# MCU.net
KiCad netlist of a schematic drawn in Altium Designer
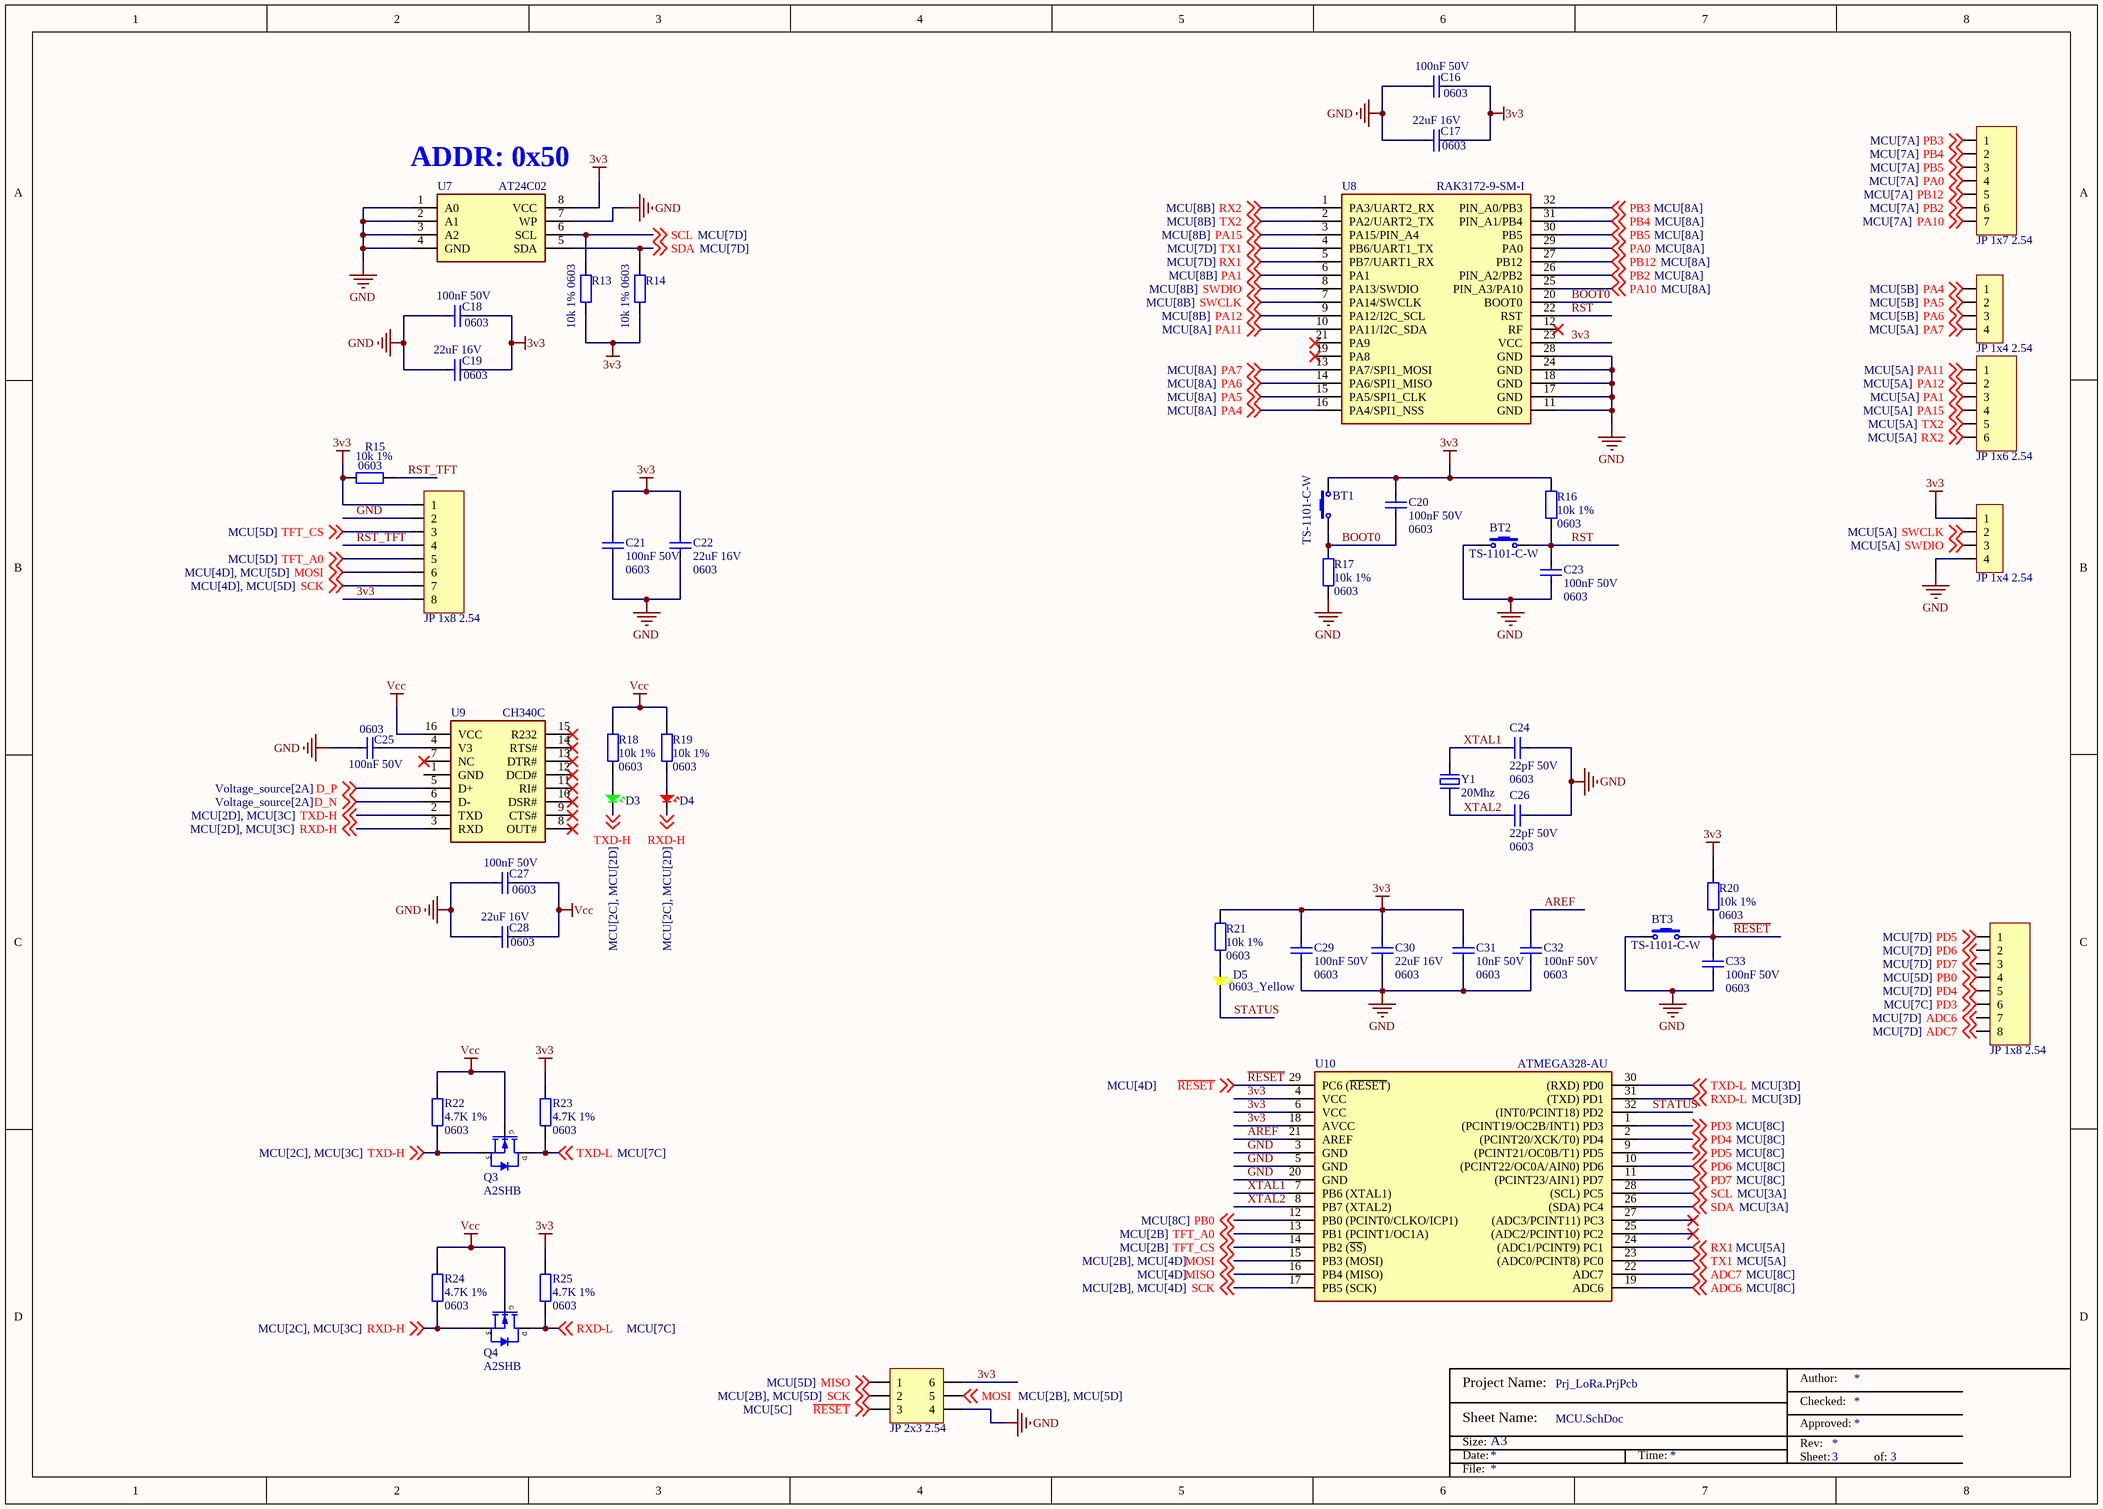
[diagram p0: MCU.SchDoc]

(export (version "E")
  (design (tool "Eeschema 10.0.6"))
  (components
    (comp (ref "BT1")
      (value "TS-1101-C-W")
      (footprint "button-2P-SMD-6x3x2.5")
      (fields (field (name "LCSC PART") "C318938") (field (name "MANUFACTURER") "XKB Connection"))
      (libsource (lib "binhbinh") (part "Button-2P"))
    )
    (comp (ref "BT2")
      (value "TS-1101-C-W")
      (footprint "button-2P-SMD-6x3x2.5")
      (fields (field (name "LCSC PART") "C318938") (field (name "MANUFACTURER") "XKB Connection"))
      (libsource (lib "binhbinh") (part "Button-2P"))
    )
    (comp (ref "BT3")
      (value "TS-1101-C-W")
      (footprint "button-2P-SMD-6x3x2.5")
      (fields (field (name "LCSC PART") "C318938") (field (name "MANUFACTURER") "XKB Connection"))
      (libsource (lib "binhbinh") (part "Button-2P"))
    )
    (comp (ref "C16")
      (value "100nF 50V")
      (footprint "C_0603")
      (description "50V 100nF X7R ±10% 0603 Multilayer Ceramic Capacitors MLCC - SMD/SMT ROHS")
      (fields
        (field (name "MANUFACTURER") "YAGEO")
        (field (name "MRF.PART") "CC0603KRX7R9BB104")
        (field (name "PACKAGE") "0603")
      )
      (libsource (lib "binhbinh") (part "C0603_MLCC_100nF_50V"))
    )
    (comp (ref "C17")
      (value "22uF 16V")
      (footprint "C_0603")
      (description "16V 22uF X5R ±20% 0603 Multilayer Ceramic Capacitors MLCC - SMD/SMT ROHS")
      (fields
        (field (name "MANUFACTURER") "Samsung Electro-Mechanics")
        (field (name "MRF.PART") "CL10A226MO7JZNC")
        (field (name "PACKAGE") "0603")
      )
      (libsource (lib "binhbinh") (part "C0603_MLCC_22uF_16V"))
    )
    (comp (ref "C18")
      (value "100nF 50V")
      (footprint "C_0603")
      (description "50V 100nF X7R ±10% 0603 Multilayer Ceramic Capacitors MLCC - SMD/SMT ROHS")
      (fields
        (field (name "MANUFACTURER") "YAGEO")
        (field (name "MRF.PART") "CC0603KRX7R9BB104")
        (field (name "PACKAGE") "0603")
      )
      (libsource (lib "binhbinh") (part "C0603_MLCC_100nF_50V"))
    )
    (comp (ref "C19")
      (value "22uF 16V")
      (footprint "C_0603")
      (description "16V 22uF X5R ±20% 0603 Multilayer Ceramic Capacitors MLCC - SMD/SMT ROHS")
      (fields
        (field (name "MANUFACTURER") "Samsung Electro-Mechanics")
        (field (name "MRF.PART") "CL10A226MO7JZNC")
        (field (name "PACKAGE") "0603")
      )
      (libsource (lib "binhbinh") (part "C0603_MLCC_22uF_16V"))
    )
    (comp (ref "C20")
      (value "100nF 50V")
      (footprint "C_0603")
      (description "50V 100nF X7R ±10% 0603 Multilayer Ceramic Capacitors MLCC - SMD/SMT ROHS")
      (fields
        (field (name "MANUFACTURER") "YAGEO")
        (field (name "MRF.PART") "CC0603KRX7R9BB104")
        (field (name "PACKAGE") "0603")
      )
      (libsource (lib "binhbinh") (part "C0603_MLCC_100nF_50V"))
    )
    (comp (ref "C21")
      (value "100nF 50V")
      (footprint "C_0603")
      (description "50V 100nF X7R ±10% 0603 Multilayer Ceramic Capacitors MLCC - SMD/SMT ROHS")
      (fields
        (field (name "MANUFACTURER") "YAGEO")
        (field (name "MRF.PART") "CC0603KRX7R9BB104")
        (field (name "PACKAGE") "0603")
      )
      (libsource (lib "binhbinh") (part "C0603_MLCC_100nF_50V"))
    )
    (comp (ref "C22")
      (value "22uF 16V")
      (footprint "C_0603")
      (description "16V 22uF X5R ±20% 0603 Multilayer Ceramic Capacitors MLCC - SMD/SMT ROHS")
      (fields
        (field (name "MANUFACTURER") "Samsung Electro-Mechanics")
        (field (name "MRF.PART") "CL10A226MO7JZNC")
        (field (name "PACKAGE") "0603")
      )
      (libsource (lib "binhbinh") (part "C0603_MLCC_22uF_16V"))
    )
    (comp (ref "C23")
      (value "100nF 50V")
      (footprint "C_0603")
      (description "50V 100nF X7R ±10% 0603 Multilayer Ceramic Capacitors MLCC - SMD/SMT ROHS")
      (fields
        (field (name "MANUFACTURER") "YAGEO")
        (field (name "MRF.PART") "CC0603KRX7R9BB104")
        (field (name "PACKAGE") "0603")
      )
      (libsource (lib "binhbinh") (part "C0603_MLCC_100nF_50V"))
    )
    (comp (ref "C24")
      (value "22pF 50V")
      (footprint "C_0603")
      (description "50V 22pF NP0 ±5% 0603 Multilayer Ceramic Capacitors MLCC - SMD/SMT ROHS")
      (fields
        (field (name "MANUFACTURER") "YAGEO")
        (field (name "MRF.PART") "CC0603JRNPO9BN220")
        (field (name "PACKAGE") "0603")
      )
      (libsource (lib "binhbinh") (part "C0603_MLCC_22pF_50V"))
    )
    (comp (ref "C25")
      (value "100nF 50V")
      (footprint "C_0603")
      (description "50V 100nF X7R ±10% 0603 Multilayer Ceramic Capacitors MLCC - SMD/SMT ROHS")
      (fields
        (field (name "MANUFACTURER") "YAGEO")
        (field (name "MRF.PART") "CC0603KRX7R9BB104")
        (field (name "PACKAGE") "0603")
      )
      (libsource (lib "binhbinh") (part "C0603_MLCC_100nF_50V"))
    )
    (comp (ref "C26")
      (value "22pF 50V")
      (footprint "C_0603")
      (description "50V 22pF NP0 ±5% 0603 Multilayer Ceramic Capacitors MLCC - SMD/SMT ROHS")
      (fields
        (field (name "MANUFACTURER") "YAGEO")
        (field (name "MRF.PART") "CC0603JRNPO9BN220")
        (field (name "PACKAGE") "0603")
      )
      (libsource (lib "binhbinh") (part "C0603_MLCC_22pF_50V"))
    )
    (comp (ref "C27")
      (value "100nF 50V")
      (footprint "C_0603")
      (description "50V 100nF X7R ±10% 0603 Multilayer Ceramic Capacitors MLCC - SMD/SMT ROHS")
      (fields
        (field (name "MANUFACTURER") "YAGEO")
        (field (name "MRF.PART") "CC0603KRX7R9BB104")
        (field (name "PACKAGE") "0603")
      )
      (libsource (lib "binhbinh") (part "C0603_MLCC_100nF_50V"))
    )
    (comp (ref "C28")
      (value "22uF 16V")
      (footprint "C_0603")
      (description "16V 22uF X5R ±20% 0603 Multilayer Ceramic Capacitors MLCC - SMD/SMT ROHS")
      (fields
        (field (name "MANUFACTURER") "Samsung Electro-Mechanics")
        (field (name "MRF.PART") "CL10A226MO7JZNC")
        (field (name "PACKAGE") "0603")
      )
      (libsource (lib "binhbinh") (part "C0603_MLCC_22uF_16V"))
    )
    (comp (ref "C29")
      (value "100nF 50V")
      (footprint "C_0603")
      (description "50V 100nF X7R ±10% 0603 Multilayer Ceramic Capacitors MLCC - SMD/SMT ROHS")
      (fields
        (field (name "MANUFACTURER") "YAGEO")
        (field (name "MRF.PART") "CC0603KRX7R9BB104")
        (field (name "PACKAGE") "0603")
      )
      (libsource (lib "binhbinh") (part "C0603_MLCC_100nF_50V"))
    )
    (comp (ref "C30")
      (value "22uF 16V")
      (footprint "C_0603")
      (description "16V 22uF X5R ±20% 0603 Multilayer Ceramic Capacitors MLCC - SMD/SMT ROHS")
      (fields
        (field (name "MANUFACTURER") "Samsung Electro-Mechanics")
        (field (name "MRF.PART") "CL10A226MO7JZNC")
        (field (name "PACKAGE") "0603")
      )
      (libsource (lib "binhbinh") (part "C0603_MLCC_22uF_16V"))
    )
    (comp (ref "C31")
      (value "10nF 50V")
      (footprint "C_0603")
      (description "50V 10nF X7R ±10% 0603 Multilayer Ceramic Capacitors MLCC - SMD/SMT ROHS")
      (fields
        (field (name "MANUFACTURER") "YAGEO")
        (field (name "MRF.PART") "CC0603KRX7R9BB103")
        (field (name "PACKAGE") "0603")
      )
      (libsource (lib "binhbinh") (part "C0603_MLCC_10nF_50V"))
    )
    (comp (ref "C32")
      (value "100nF 50V")
      (footprint "C_0603")
      (description "50V 100nF X7R ±10% 0603 Multilayer Ceramic Capacitors MLCC - SMD/SMT ROHS")
      (fields
        (field (name "MANUFACTURER") "YAGEO")
        (field (name "MRF.PART") "CC0603KRX7R9BB104")
        (field (name "PACKAGE") "0603")
      )
      (libsource (lib "binhbinh") (part "C0603_MLCC_100nF_50V"))
    )
    (comp (ref "C33")
      (value "100nF 50V")
      (footprint "C_0603")
      (description "50V 100nF X7R ±10% 0603 Multilayer Ceramic Capacitors MLCC - SMD/SMT ROHS")
      (fields
        (field (name "MANUFACTURER") "YAGEO")
        (field (name "MRF.PART") "CC0603KRX7R9BB104")
        (field (name "PACKAGE") "0603")
      )
      (libsource (lib "binhbinh") (part "C0603_MLCC_100nF_50V"))
    )
    (comp (ref "D3")
      (value "0603 GREEN")
      (footprint "LED0603_GREEN")
      (fields (field (name "MANUFACTURER") "Amicc") (field (name "MRF.PART") "A-SP192DGHC-C01-4T"))
      (libsource (lib "binhbinh") (part "L0603_GREEN"))
    )
    (comp (ref "D4")
      (value "0603 RED")
      (footprint "LED0603_RED")
      (fields (field (name "MANUFACTURER") "XINGLIGHT") (field (name "MRF.PART") "XL-1608SURC-06"))
      (libsource (lib "binhbinh") (part "L0603_RED"))
    )
    (comp (ref "D5")
      (value "0603_Yellow")
      (footprint "LED0603_YELLOW")
      (fields
        (field (name "LCSC PART") "C965802")
        (field (name "MRF.PART") "XL-1608UYC-06")
        (field (name "MANUFACTURER") "XINGLIGHT")
      )
      (libsource (lib "binhbinh") (part "L0603_Yellow"))
    )
    (comp (ref "JP2")
      (value "JP 1x7 2.54")
      (footprint "JP 1x7 CT")
      (description "Cắm")
      (libsource (lib "Altium_Lib_by_KhueNguyenCreator") (part "JP 1x7 2.54 Cai Thang"))
    )
    (comp (ref "JP3")
      (value "JP 1x4 2.54")
      (footprint "JP 1x4 CT")
      (description "Cắm")
      (libsource (lib "Altium_Lib_by_KhueNguyenCreator") (part "JP 1x4 2.54 Cai Thang"))
    )
    (comp (ref "JP4")
      (value "JP 1x6 2.54")
      (footprint "JP 1x6 CT")
      (description "Cắm")
      (libsource (lib "Altium_Lib_by_KhueNguyenCreator") (part "JP 1x6 2.54 Cai Thang"))
    )
    (comp (ref "JP5")
      (value "JP 1x8 2.54")
      (footprint "JP 1x8 CT")
      (description "Cắm")
      (libsource (lib "Altium_Lib_by_KhueNguyenCreator") (part "JP 1x8 2.54 Cai Thang"))
    )
    (comp (ref "JP6")
      (value "JP 1x4 2.54")
      (footprint "JP 1x4 CT")
      (description "Cắm")
      (libsource (lib "Altium_Lib_by_KhueNguyenCreator") (part "JP 1x4 2.54 Cai Thang"))
    )
    (comp (ref "JP7")
      (value "JP 1x8 2.54")
      (footprint "JP 1x8 CT")
      (description "Cắm")
      (libsource (lib "Altium_Lib_by_KhueNguyenCreator") (part "JP 1x8 2.54 Cai Thang"))
    )
    (comp (ref "JP8")
      (value "JP 2x3 2.54")
      (footprint "JP 2x3 DT")
      (description "Cắm")
      (libsource (lib "Altium_Lib_by_KhueNguyenCreator") (part "JP 2x3 2.54 Duc Thang"))
    )
    (comp (ref "Q3")
      (value "A2SHB")
      (footprint "SOT23-3")
      (description "20V 3A 900mW 60mΩ@4.5V 1V@50uA 1 N-Channel SOT-23 MOSFETs ROHS")
      (fields (field (name "LCSC PART") "C2905536") (field (name "MRF.PART") "JSM2302A-A2SHB"))
      (libsource (lib "binhbinh") (part "A2SHB"))
    )
    (comp (ref "Q4")
      (value "A2SHB")
      (footprint "SOT23-3")
      (description "20V 3A 900mW 60mΩ@4.5V 1V@50uA 1 N-Channel SOT-23 MOSFETs ROHS")
      (fields (field (name "LCSC PART") "C2905536") (field (name "MRF.PART") "JSM2302A-A2SHB"))
      (libsource (lib "binhbinh") (part "A2SHB"))
    )
    (comp (ref "R13")
      (value "10k 1%")
      (footprint "R_0603")
      (description "100mW Thick Film Resistor 75V ±100ppm/℃ ±1% 10kΩ 0603 Chip Resistor - Surface Mount ROHS")
      (fields
        (field (name "LCSC PART") "C98220")
        (field (name "MRF.PART") "RC0603FR-0710KL")
        (field (name "PACKAGE") "0603")
      )
      (libsource (lib "binhbinh") (part "R0603_10k"))
    )
    (comp (ref "R14")
      (value "10k 1%")
      (footprint "R_0603")
      (description "100mW Thick Film Resistor 75V ±100ppm/℃ ±1% 10kΩ 0603 Chip Resistor - Surface Mount ROHS")
      (fields
        (field (name "LCSC PART") "C98220")
        (field (name "MRF.PART") "RC0603FR-0710KL")
        (field (name "PACKAGE") "0603")
      )
      (libsource (lib "binhbinh") (part "R0603_10k"))
    )
    (comp (ref "R15")
      (value "10k 1%")
      (footprint "R_0603")
      (description "100mW Thick Film Resistor 75V ±100ppm/℃ ±1% 10kΩ 0603 Chip Resistor - Surface Mount ROHS")
      (fields
        (field (name "LCSC PART") "C98220")
        (field (name "MRF.PART") "RC0603FR-0710KL")
        (field (name "PACKAGE") "0603")
      )
      (libsource (lib "") (part "R0603_10k_1"))
    )
    (comp (ref "R16")
      (value "10k 1%")
      (footprint "R_0603")
      (description "100mW Thick Film Resistor 75V ±100ppm/℃ ±1% 10kΩ 0603 Chip Resistor - Surface Mount ROHS")
      (fields
        (field (name "LCSC PART") "C98220")
        (field (name "MRF.PART") "RC0603FR-0710KL")
        (field (name "PACKAGE") "0603")
      )
      (libsource (lib "binhbinh") (part "R0603_10k"))
    )
    (comp (ref "R17")
      (value "10k 1%")
      (footprint "R_0603")
      (description "100mW Thick Film Resistor 75V ±100ppm/℃ ±1% 10kΩ 0603 Chip Resistor - Surface Mount ROHS")
      (fields
        (field (name "LCSC PART") "C98220")
        (field (name "MRF.PART") "RC0603FR-0710KL")
        (field (name "PACKAGE") "0603")
      )
      (libsource (lib "binhbinh") (part "R0603_10k"))
    )
    (comp (ref "R18")
      (value "10k 1%")
      (footprint "R_0603")
      (description "100mW Thick Film Resistor 75V ±100ppm/℃ ±1% 10kΩ 0603 Chip Resistor - Surface Mount ROHS")
      (fields
        (field (name "LCSC PART") "C98220")
        (field (name "MRF.PART") "RC0603FR-0710KL")
        (field (name "PACKAGE") "0603")
      )
      (libsource (lib "binhbinh") (part "R0603_10k"))
    )
    (comp (ref "R19")
      (value "10k 1%")
      (footprint "R_0603")
      (description "100mW Thick Film Resistor 75V ±100ppm/℃ ±1% 10kΩ 0603 Chip Resistor - Surface Mount ROHS")
      (fields
        (field (name "LCSC PART") "C98220")
        (field (name "MRF.PART") "RC0603FR-0710KL")
        (field (name "PACKAGE") "0603")
      )
      (libsource (lib "binhbinh") (part "R0603_10k"))
    )
    (comp (ref "R20")
      (value "10k 1%")
      (footprint "R_0603")
      (description "100mW Thick Film Resistor 75V ±100ppm/℃ ±1% 10kΩ 0603 Chip Resistor - Surface Mount ROHS")
      (fields
        (field (name "LCSC PART") "C98220")
        (field (name "MRF.PART") "RC0603FR-0710KL")
        (field (name "PACKAGE") "0603")
      )
      (libsource (lib "binhbinh") (part "R0603_10k"))
    )
    (comp (ref "R21")
      (value "10k 1%")
      (footprint "R_0603")
      (description "100mW Thick Film Resistor 75V ±100ppm/℃ ±1% 10kΩ 0603 Chip Resistor - Surface Mount ROHS")
      (fields
        (field (name "LCSC PART") "C98220")
        (field (name "MRF.PART") "RC0603FR-0710KL")
        (field (name "PACKAGE") "0603")
      )
      (libsource (lib "binhbinh") (part "R0603_10k"))
    )
    (comp (ref "R22")
      (value "4.7K 1%")
      (footprint "R_0603")
      (description "4.7 kOhms ±1% 0.1W, 1/10W Chip Resistor 0603 (1608 Metric) Moisture Resistant Thick Film")
      (fields
        (field (name "MANUFACTURER") "YAGEO")
        (field (name "MRF.PART") "RC0603FR-074K7L")
        (field (name "PACKAGE") "0603")
      )
      (libsource (lib "binhbinh") (part "R0603_4.7K"))
    )
    (comp (ref "R23")
      (value "4.7K 1%")
      (footprint "R_0603")
      (description "4.7 kOhms ±1% 0.1W, 1/10W Chip Resistor 0603 (1608 Metric) Moisture Resistant Thick Film")
      (fields
        (field (name "MANUFACTURER") "YAGEO")
        (field (name "MRF.PART") "RC0603FR-074K7L")
        (field (name "PACKAGE") "0603")
      )
      (libsource (lib "binhbinh") (part "R0603_4.7K"))
    )
    (comp (ref "R24")
      (value "4.7K 1%")
      (footprint "R_0603")
      (description "4.7 kOhms ±1% 0.1W, 1/10W Chip Resistor 0603 (1608 Metric) Moisture Resistant Thick Film")
      (fields
        (field (name "MANUFACTURER") "YAGEO")
        (field (name "MRF.PART") "RC0603FR-074K7L")
        (field (name "PACKAGE") "0603")
      )
      (libsource (lib "binhbinh") (part "R0603_4.7K"))
    )
    (comp (ref "R25")
      (value "4.7K 1%")
      (footprint "R_0603")
      (description "4.7 kOhms ±1% 0.1W, 1/10W Chip Resistor 0603 (1608 Metric) Moisture Resistant Thick Film")
      (fields
        (field (name "MANUFACTURER") "YAGEO")
        (field (name "MRF.PART") "RC0603FR-074K7L")
        (field (name "PACKAGE") "0603")
      )
      (libsource (lib "binhbinh") (part "R0603_4.7K"))
    )
    (comp (ref "U7")
      (value "AT24C02")
      (footprint "SOP-8")
      (description "2Kbit 1MHz I2C SOP-8 EEPROM ROHS")
      (fields (field (name "LCSC PART") "C7470930") (field (name "MANUFACTURER") "HXY MOSFET"))
      (libsource (lib "binhbinh") (part "AT24C02"))
    )
    (comp (ref "U8")
      (value "RAK3172-9-SM-I")
      (footprint "RAK3172")
      (description "15km SMD,15.5x15mm LoRa Modules ROHS, with IPEX")
      (fields (field (name "LCSC PART") "C19723905") (field (name "MANUFACTURER") "RAKwireless"))
      (libsource (lib "binhbinh") (part "RAK3172-9-SM-I"))
    )
    (comp (ref "U9")
      (value "CH340C")
      (footprint "CH340C")
      (description "2Mbps Transceiver USB 2.0 SOP-16 USB Converters ROHS")
      (fields (field (name "LCSC PART") "C84681") (field (name "MANUFACTURER") "WCH"))
      (libsource (lib "binhbinh") (part "CH340C"))
    )
    (comp (ref "U10")
      (value "ATMEGA328-AU")
      (footprint "TQFP-32(7x7)")
      (description "AVR 20MHz TQFP-32(7x7) Microcontrollers (MCU/MPU/SOC) ROHS")
      (fields (field (name "LCSC PART") "C618731") (field (name "MANUFACTURER") "MICROCHIP"))
      (libsource (lib "binhbinh") (part "ATMEGA328-AU"))
    )
    (comp (ref "Y1")
      (value "20Mhz")
      (footprint "HC-49S-SMD")
      (description "20MHz Crystal Oscillator 20pF ±20ppm ±30ppm HC-49S-SMD Crystals ROHS")
      (fields (field (name "LCSC PART") "C18213020") (field (name "MRF.PART") "H6OEL89CSC-SUGYLC-20M"))
      (libsource (lib "binhbinh") (part "20Mhz-2P"))
    )
  )
  (nets
    (net (code "1") (name "/AREF") (class "Default")
      (node (ref "C32") (pin "2") (pinfunction "2_2") (pintype "passive"))
      (node (ref "U10") (pin "21") (pinfunction "AREF_21") (pintype "passive"))
    )
    (net (code "2") (name "/BOOT0") (class "Default")
      (node (ref "BT1") (pin "1") (pinfunction "1_1") (pintype "passive"))
      (node (ref "C20") (pin "2") (pinfunction "2_2") (pintype "passive"))
      (node (ref "R17") (pin "2") (pinfunction "2_2") (pintype "passive"))
      (node (ref "U8") (pin "20") (pinfunction "BOOT0_20") (pintype "passive"))
    )
    (net (code "3") (name "/RST") (class "Default")
      (node (ref "BT2") (pin "2") (pinfunction "2_2") (pintype "passive"))
      (node (ref "C23") (pin "2") (pinfunction "2_2") (pintype "passive"))
      (node (ref "R16") (pin "1") (pinfunction "1_1") (pintype "passive"))
      (node (ref "U8") (pin "22") (pinfunction "RST_22") (pintype "passive"))
    )
    (net (code "4") (name "/RST_TFT") (class "Default")
      (node (ref "JP5") (pin "4") (pinfunction "4_4") (pintype "passive"))
      (node (ref "R15") (pin "2") (pinfunction "2_2") (pintype "passive"))
    )
    (net (code "5") (name "/STATUS") (class "Default")
      (node (ref "D5") (pin "2") (pinfunction "2_2") (pintype "passive"))
      (node (ref "U10") (pin "32") (pinfunction "(INT0/PCINT18)_PD2_32") (pintype "passive"))
    )
    (net (code "6") (name "/XTAL1") (class "Default")
      (node (ref "C24") (pin "2") (pinfunction "2_2") (pintype "passive"))
      (node (ref "U10") (pin "7") (pinfunction "PB6_(XTAL1)_7") (pintype "passive"))
      (node (ref "Y1") (pin "2") (pinfunction "2_2") (pintype "passive"))
    )
    (net (code "7") (name "/XTAL2") (class "Default")
      (node (ref "C26") (pin "2") (pinfunction "2_2") (pintype "passive"))
      (node (ref "U10") (pin "8") (pinfunction "PB7_(XTAL2)_8") (pintype "passive"))
      (node (ref "Y1") (pin "1") (pinfunction "1_1") (pintype "passive"))
    )
    (net (code "8") (name "3v3") (class "Default")
      (node (ref "BT1") (pin "2") (pinfunction "2_2") (pintype "passive"))
      (node (ref "C16") (pin "2") (pinfunction "2_2") (pintype "passive"))
      (node (ref "C17") (pin "1") (pinfunction "1_1") (pintype "passive"))
      (node (ref "C18") (pin "2") (pinfunction "2_2") (pintype "passive"))
      (node (ref "C19") (pin "1") (pinfunction "1_1") (pintype "passive"))
      (node (ref "C20") (pin "1") (pinfunction "1_1") (pintype "passive"))
      (node (ref "C21") (pin "2") (pinfunction "2_2") (pintype "passive"))
      (node (ref "C22") (pin "1") (pinfunction "1_1") (pintype "passive"))
      (node (ref "C29") (pin "2") (pinfunction "2_2") (pintype "passive"))
      (node (ref "C30") (pin "1") (pinfunction "1_1") (pintype "passive"))
      (node (ref "C31") (pin "2") (pinfunction "2_2") (pintype "passive"))
      (node (ref "JP5") (pin "1") (pinfunction "1_1") (pintype "passive"))
      (node (ref "JP5") (pin "8") (pinfunction "8_8") (pintype "passive"))
      (node (ref "JP6") (pin "1") (pinfunction "1_1") (pintype "passive"))
      (node (ref "JP8") (pin "6") (pinfunction "6_6") (pintype "passive"))
      (node (ref "R13") (pin "1") (pinfunction "1_1") (pintype "passive"))
      (node (ref "R14") (pin "1") (pinfunction "1_1") (pintype "passive"))
      (node (ref "R15") (pin "1") (pinfunction "1_1") (pintype "passive"))
      (node (ref "R16") (pin "2") (pinfunction "2_2") (pintype "passive"))
      (node (ref "R20") (pin "2") (pinfunction "2_2") (pintype "passive"))
      (node (ref "R21") (pin "2") (pinfunction "2_2") (pintype "passive"))
      (node (ref "R23") (pin "2") (pinfunction "2_2") (pintype "passive"))
      (node (ref "R25") (pin "2") (pinfunction "2_2") (pintype "passive"))
      (node (ref "U10") (pin "18") (pinfunction "AVCC_18") (pintype "passive"))
      (node (ref "U10") (pin "4") (pinfunction "VCC_4") (pintype "passive"))
      (node (ref "U10") (pin "6") (pinfunction "VCC_6") (pintype "passive"))
      (node (ref "U7") (pin "8") (pinfunction "VCC_8") (pintype "passive"))
      (node (ref "U8") (pin "23") (pinfunction "VCC_23") (pintype "passive"))
    )
    (net (code "9") (name "ADC6") (class "Default")
      (node (ref "JP7") (pin "7") (pinfunction "7_7") (pintype "passive"))
      (node (ref "U10") (pin "19") (pinfunction "ADC6_19") (pintype "passive"))
    )
    (net (code "10") (name "ADC7") (class "Default")
      (node (ref "JP7") (pin "8") (pinfunction "8_8") (pintype "passive"))
      (node (ref "U10") (pin "22") (pinfunction "ADC7_22") (pintype "passive"))
    )
    (net (code "11") (name "D_N") (class "Default")
      (node (ref "U9") (pin "6") (pinfunction "D-_6") (pintype "passive"))
    )
    (net (code "12") (name "D_P") (class "Default")
      (node (ref "U9") (pin "5") (pinfunction "D+_5") (pintype "passive"))
    )
    (net (code "13") (name "GND") (class "Default")
      (node (ref "BT2") (pin "1") (pinfunction "1_1") (pintype "passive"))
      (node (ref "BT3") (pin "1") (pinfunction "1_1") (pintype "passive"))
      (node (ref "C16") (pin "1") (pinfunction "1_1") (pintype "passive"))
      (node (ref "C17") (pin "2") (pinfunction "2_2") (pintype "passive"))
      (node (ref "C18") (pin "1") (pinfunction "1_1") (pintype "passive"))
      (node (ref "C19") (pin "2") (pinfunction "2_2") (pintype "passive"))
      (node (ref "C21") (pin "1") (pinfunction "1_1") (pintype "passive"))
      (node (ref "C22") (pin "2") (pinfunction "2_2") (pintype "passive"))
      (node (ref "C23") (pin "1") (pinfunction "1_1") (pintype "passive"))
      (node (ref "C24") (pin "1") (pinfunction "1_1") (pintype "passive"))
      (node (ref "C25") (pin "2") (pinfunction "2_2") (pintype "passive"))
      (node (ref "C26") (pin "1") (pinfunction "1_1") (pintype "passive"))
      (node (ref "C27") (pin "1") (pinfunction "1_1") (pintype "passive"))
      (node (ref "C28") (pin "2") (pinfunction "2_2") (pintype "passive"))
      (node (ref "C29") (pin "1") (pinfunction "1_1") (pintype "passive"))
      (node (ref "C30") (pin "2") (pinfunction "2_2") (pintype "passive"))
      (node (ref "C31") (pin "1") (pinfunction "1_1") (pintype "passive"))
      (node (ref "C32") (pin "1") (pinfunction "1_1") (pintype "passive"))
      (node (ref "C33") (pin "1") (pinfunction "1_1") (pintype "passive"))
      (node (ref "JP5") (pin "2") (pinfunction "2_2") (pintype "passive"))
      (node (ref "JP6") (pin "4") (pinfunction "4_4") (pintype "passive"))
      (node (ref "JP8") (pin "4") (pinfunction "4_4") (pintype "passive"))
      (node (ref "R17") (pin "1") (pinfunction "1_1") (pintype "passive"))
      (node (ref "U10") (pin "20") (pinfunction "GND_20") (pintype "passive"))
      (node (ref "U10") (pin "3") (pinfunction "GND_3") (pintype "passive"))
      (node (ref "U10") (pin "5") (pinfunction "GND_5") (pintype "passive"))
      (node (ref "U7") (pin "1") (pinfunction "A0_1") (pintype "passive"))
      (node (ref "U7") (pin "2") (pinfunction "A1_2") (pintype "passive"))
      (node (ref "U7") (pin "3") (pinfunction "A2_3") (pintype "passive"))
      (node (ref "U7") (pin "4") (pinfunction "GND_4") (pintype "passive"))
      (node (ref "U7") (pin "7") (pinfunction "WP_7") (pintype "passive"))
      (node (ref "U8") (pin "11") (pinfunction "GND_11") (pintype "passive"))
      (node (ref "U8") (pin "17") (pinfunction "GND_17") (pintype "passive"))
      (node (ref "U8") (pin "18") (pinfunction "GND_18") (pintype "passive"))
      (node (ref "U8") (pin "24") (pinfunction "GND_24") (pintype "passive"))
      (node (ref "U8") (pin "28") (pinfunction "GND_28") (pintype "passive"))
    )
    (net (code "14") (name "MISO") (class "Default")
      (node (ref "JP8") (pin "1") (pinfunction "1_1") (pintype "passive"))
      (node (ref "U10") (pin "16") (pinfunction "PB4_(MISO)_16") (pintype "passive"))
    )
    (net (code "15") (name "MOSI") (class "Default")
      (node (ref "JP5") (pin "6") (pinfunction "6_6") (pintype "passive"))
      (node (ref "JP8") (pin "5") (pinfunction "5_5") (pintype "passive"))
      (node (ref "U10") (pin "15") (pinfunction "PB3_(MOSI)_15") (pintype "passive"))
    )
    (net (code "16") (name "Net-(D3-Pad1)") (class "Default")
      (node (ref "D3") (pin "1") (pinfunction "1_1") (pintype "passive"))
      (node (ref "R18") (pin "1") (pinfunction "1_1") (pintype "passive"))
    )
    (net (code "17") (name "Net-(D4-Pad1)") (class "Default")
      (node (ref "D4") (pin "1") (pinfunction "1_1") (pintype "passive"))
      (node (ref "R19") (pin "1") (pinfunction "1_1") (pintype "passive"))
    )
    (net (code "18") (name "Net-(D5-Pad1)") (class "Default")
      (node (ref "D5") (pin "1") (pinfunction "1_1") (pintype "passive"))
      (node (ref "R21") (pin "1") (pinfunction "1_1") (pintype "passive"))
    )
    (net (code "19") (name "Net-(U9-V3)") (class "Default")
      (node (ref "C25") (pin "1") (pinfunction "1_1") (pintype "passive"))
      (node (ref "U9") (pin "4") (pinfunction "V3_4") (pintype "passive"))
    )
    (net (code "20") (name "PA0") (class "Default")
      (node (ref "JP2") (pin "4") (pinfunction "4_4") (pintype "passive"))
      (node (ref "U8") (pin "29") (pinfunction "PA0_29") (pintype "passive"))
    )
    (net (code "21") (name "PA1") (class "Default")
      (node (ref "JP4") (pin "3") (pinfunction "3_3") (pintype "passive"))
      (node (ref "U8") (pin "6") (pinfunction "PA1_6") (pintype "passive"))
    )
    (net (code "22") (name "PA4") (class "Default")
      (node (ref "JP3") (pin "1") (pinfunction "1_1") (pintype "passive"))
      (node (ref "U8") (pin "16") (pinfunction "PA4/SPI1_NSS_16") (pintype "passive"))
    )
    (net (code "23") (name "PA5") (class "Default")
      (node (ref "JP3") (pin "2") (pinfunction "2_2") (pintype "passive"))
      (node (ref "U8") (pin "15") (pinfunction "PA5/SPI1_CLK_15") (pintype "passive"))
    )
    (net (code "24") (name "PA6") (class "Default")
      (node (ref "JP3") (pin "3") (pinfunction "3_3") (pintype "passive"))
      (node (ref "U8") (pin "14") (pinfunction "PA6/SPI1_MISO_14") (pintype "passive"))
    )
    (net (code "25") (name "PA7") (class "Default")
      (node (ref "JP3") (pin "4") (pinfunction "4_4") (pintype "passive"))
      (node (ref "U8") (pin "13") (pinfunction "PA7/SPI1_MOSI_13") (pintype "passive"))
    )
    (net (code "26") (name "PA10") (class "Default")
      (node (ref "JP2") (pin "7") (pinfunction "7_7") (pintype "passive"))
      (node (ref "U8") (pin "25") (pinfunction "PIN_A3/PA10_25") (pintype "passive"))
    )
    (net (code "27") (name "PA11") (class "Default")
      (node (ref "JP4") (pin "1") (pinfunction "1_1") (pintype "passive"))
      (node (ref "U8") (pin "10") (pinfunction "PA11/I2C_SDA_10") (pintype "passive"))
    )
    (net (code "28") (name "PA12") (class "Default")
      (node (ref "JP4") (pin "2") (pinfunction "2_2") (pintype "passive"))
      (node (ref "U8") (pin "9") (pinfunction "PA12/I2C_SCL_9") (pintype "passive"))
    )
    (net (code "29") (name "PA15") (class "Default")
      (node (ref "JP4") (pin "4") (pinfunction "4_4") (pintype "passive"))
      (node (ref "U8") (pin "3") (pinfunction "PA15/PIN_A4_3") (pintype "passive"))
    )
    (net (code "30") (name "PB0") (class "Default")
      (node (ref "JP7") (pin "4") (pinfunction "4_4") (pintype "passive"))
      (node (ref "U10") (pin "12") (pinfunction "PB0_(PCINT0/CLKO/ICP1)_12") (pintype "passive"))
    )
    (net (code "31") (name "PB2") (class "Default")
      (node (ref "JP2") (pin "6") (pinfunction "6_6") (pintype "passive"))
      (node (ref "U8") (pin "26") (pinfunction "PIN_A2/PB2_26") (pintype "passive"))
    )
    (net (code "32") (name "PB3") (class "Default")
      (node (ref "JP2") (pin "1") (pinfunction "1_1") (pintype "passive"))
      (node (ref "U8") (pin "32") (pinfunction "PIN_A0/PB3_32") (pintype "passive"))
    )
    (net (code "33") (name "PB4") (class "Default")
      (node (ref "JP2") (pin "2") (pinfunction "2_2") (pintype "passive"))
      (node (ref "U8") (pin "31") (pinfunction "PIN_A1/PB4_31") (pintype "passive"))
    )
    (net (code "34") (name "PB5") (class "Default")
      (node (ref "JP2") (pin "3") (pinfunction "3_3") (pintype "passive"))
      (node (ref "U8") (pin "30") (pinfunction "PB5_30") (pintype "passive"))
    )
    (net (code "35") (name "PB12") (class "Default")
      (node (ref "JP2") (pin "5") (pinfunction "5_5") (pintype "passive"))
      (node (ref "U8") (pin "27") (pinfunction "PB12_27") (pintype "passive"))
    )
    (net (code "36") (name "PD3") (class "Default")
      (node (ref "JP7") (pin "6") (pinfunction "6_6") (pintype "passive"))
      (node (ref "U10") (pin "1") (pinfunction "(PCINT19/OC2B/INT1)_PD3_1") (pintype "passive"))
    )
    (net (code "37") (name "PD4") (class "Default")
      (node (ref "JP7") (pin "5") (pinfunction "5_5") (pintype "passive"))
      (node (ref "U10") (pin "2") (pinfunction "(PCINT20/XCK/T0)_PD4_2") (pintype "passive"))
    )
    (net (code "38") (name "PD5") (class "Default")
      (node (ref "JP7") (pin "1") (pinfunction "1_1") (pintype "passive"))
      (node (ref "U10") (pin "9") (pinfunction "(PCINT21/OC0B/T1)_PD5_9") (pintype "passive"))
    )
    (net (code "39") (name "PD6") (class "Default")
      (node (ref "JP7") (pin "2") (pinfunction "2_2") (pintype "passive"))
      (node (ref "U10") (pin "10") (pinfunction "(PCINT22/OC0A/AIN0)_PD6_10") (pintype "passive"))
    )
    (net (code "40") (name "PD7") (class "Default")
      (node (ref "JP7") (pin "3") (pinfunction "3_3") (pintype "passive"))
      (node (ref "U10") (pin "11") (pinfunction "(PCINT23/AIN1)_PD7_11") (pintype "passive"))
    )
    (net (code "41") (name "RX1") (class "Default")
      (node (ref "U10") (pin "24") (pinfunction "(ADC1/PCINT9)_PC1_24") (pintype "passive"))
      (node (ref "U8") (pin "5") (pinfunction "PB7/UART1_RX_5") (pintype "passive"))
    )
    (net (code "42") (name "RX2") (class "Default")
      (node (ref "JP4") (pin "6") (pinfunction "6_6") (pintype "passive"))
      (node (ref "U8") (pin "1") (pinfunction "PA3/UART2_RX_1") (pintype "passive"))
    )
    (net (code "43") (name "RXD-H") (class "Default")
      (node (ref "D4") (pin "2") (pinfunction "2_2") (pintype "passive"))
      (node (ref "Q4") (pin "2") (pinfunction "S_2") (pintype "passive"))
      (node (ref "R24") (pin "1") (pinfunction "1_1") (pintype "passive"))
      (node (ref "U9") (pin "3") (pinfunction "RXD_3") (pintype "passive"))
    )
    (net (code "44") (name "RXD-L") (class "Default")
      (node (ref "Q4") (pin "3") (pinfunction "D_3") (pintype "passive"))
      (node (ref "R25") (pin "1") (pinfunction "1_1") (pintype "passive"))
      (node (ref "U10") (pin "31") (pinfunction "(TXD)_PD1_31") (pintype "passive"))
    )
    (net (code "45") (name "SCK") (class "Default")
      (node (ref "JP5") (pin "7") (pinfunction "7_7") (pintype "passive"))
      (node (ref "JP8") (pin "2") (pinfunction "2_2") (pintype "passive"))
      (node (ref "U10") (pin "17") (pinfunction "PB5_(SCK)_17") (pintype "passive"))
    )
    (net (code "46") (name "SCL") (class "Default")
      (node (ref "R13") (pin "2") (pinfunction "2_2") (pintype "passive"))
      (node (ref "U10") (pin "28") (pinfunction "(SCL)_PC5_28") (pintype "passive"))
      (node (ref "U7") (pin "6") (pinfunction "SCL_6") (pintype "passive"))
    )
    (net (code "47") (name "SDA") (class "Default")
      (node (ref "R14") (pin "2") (pinfunction "2_2") (pintype "passive"))
      (node (ref "U10") (pin "26") (pinfunction "(SDA)_PC4_26") (pintype "passive"))
      (node (ref "U7") (pin "5") (pinfunction "SDA_5") (pintype "passive"))
    )
    (net (code "48") (name "SWCLK") (class "Default")
      (node (ref "JP6") (pin "2") (pinfunction "2_2") (pintype "passive"))
      (node (ref "U8") (pin "7") (pinfunction "PA14/SWCLK_7") (pintype "passive"))
    )
    (net (code "49") (name "SWDIO") (class "Default")
      (node (ref "JP6") (pin "3") (pinfunction "3_3") (pintype "passive"))
      (node (ref "U8") (pin "8") (pinfunction "PA13/SWDIO_8") (pintype "passive"))
    )
    (net (code "50") (name "TFT_A0") (class "Default")
      (node (ref "JP5") (pin "5") (pinfunction "5_5") (pintype "passive"))
      (node (ref "U10") (pin "13") (pinfunction "PB1_(PCINT1/OC1A)_13") (pintype "passive"))
    )
    (net (code "51") (name "TFT_CS") (class "Default")
      (node (ref "JP5") (pin "3") (pinfunction "3_3") (pintype "passive"))
      (node (ref "U10") (pin "14") (pinfunction "PB2_(~{SS})_14") (pintype "passive"))
    )
    (net (code "52") (name "TX1") (class "Default")
      (node (ref "U10") (pin "23") (pinfunction "(ADC0/PCINT8)_PC0_23") (pintype "passive"))
      (node (ref "U8") (pin "4") (pinfunction "PB6/UART1_TX_4") (pintype "passive"))
    )
    (net (code "53") (name "TX2") (class "Default")
      (node (ref "JP4") (pin "5") (pinfunction "5_5") (pintype "passive"))
      (node (ref "U8") (pin "2") (pinfunction "PA2/UART2_TX_2") (pintype "passive"))
    )
    (net (code "54") (name "TXD-H") (class "Default")
      (node (ref "D3") (pin "2") (pinfunction "2_2") (pintype "passive"))
      (node (ref "Q3") (pin "2") (pinfunction "S_2") (pintype "passive"))
      (node (ref "R22") (pin "1") (pinfunction "1_1") (pintype "passive"))
      (node (ref "U9") (pin "2") (pinfunction "TXD_2") (pintype "passive"))
    )
    (net (code "55") (name "TXD-L") (class "Default")
      (node (ref "Q3") (pin "3") (pinfunction "D_3") (pintype "passive"))
      (node (ref "R23") (pin "1") (pinfunction "1_1") (pintype "passive"))
      (node (ref "U10") (pin "30") (pinfunction "(RXD)_PD0_30") (pintype "passive"))
    )
    (net (code "56") (name "Vcc") (class "Default")
      (node (ref "C27") (pin "2") (pinfunction "2_2") (pintype "passive"))
      (node (ref "C28") (pin "1") (pinfunction "1_1") (pintype "passive"))
      (node (ref "Q3") (pin "1") (pinfunction "G_1") (pintype "passive"))
      (node (ref "Q4") (pin "1") (pinfunction "G_1") (pintype "passive"))
      (node (ref "R18") (pin "2") (pinfunction "2_2") (pintype "passive"))
      (node (ref "R19") (pin "2") (pinfunction "2_2") (pintype "passive"))
      (node (ref "R22") (pin "2") (pinfunction "2_2") (pintype "passive"))
      (node (ref "R24") (pin "2") (pinfunction "2_2") (pintype "passive"))
      (node (ref "U9") (pin "16") (pinfunction "VCC_16") (pintype "passive"))
    )
    (net (code "57") (name "unconnected-(U8-PA8-Pad19)") (class "Default")
      (node (ref "U8") (pin "19") (pinfunction "PA8_19") (pintype "passive+no_connect"))
    )
    (net (code "58") (name "unconnected-(U8-PA9-Pad21)") (class "Default")
      (node (ref "U8") (pin "21") (pinfunction "PA9_21") (pintype "passive+no_connect"))
    )
    (net (code "59") (name "unconnected-(U8-RF-Pad12)") (class "Default")
      (node (ref "U8") (pin "12") (pinfunction "RF_12") (pintype "passive+no_connect"))
    )
    (net (code "60") (name "unconnected-(U9-CTS#-Pad9)") (class "Default")
      (node (ref "U9") (pin "9") (pinfunction "CTS#_9") (pintype "passive+no_connect"))
    )
    (net (code "61") (name "unconnected-(U9-DCD#-Pad12)") (class "Default")
      (node (ref "U9") (pin "12") (pinfunction "DCD#_12") (pintype "passive+no_connect"))
    )
    (net (code "62") (name "unconnected-(U9-DSR#-Pad10)") (class "Default")
      (node (ref "U9") (pin "10") (pinfunction "DSR#_10") (pintype "passive+no_connect"))
    )
    (net (code "63") (name "unconnected-(U9-DTR#-Pad13)") (class "Default")
      (node (ref "U9") (pin "13") (pinfunction "DTR#_13") (pintype "passive+no_connect"))
    )
    (net (code "64") (name "unconnected-(U9-GND-Pad1)") (class "Default")
      (node (ref "U9") (pin "1") (pinfunction "GND_1") (pintype "passive"))
    )
    (net (code "65") (name "unconnected-(U9-NC-Pad7)") (class "Default")
      (node (ref "U9") (pin "7") (pinfunction "NC_7") (pintype "passive+no_connect"))
    )
    (net (code "66") (name "unconnected-(U9-OUT#-Pad8)") (class "Default")
      (node (ref "U9") (pin "8") (pinfunction "OUT#_8") (pintype "passive+no_connect"))
    )
    (net (code "67") (name "unconnected-(U9-R232-Pad15)") (class "Default")
      (node (ref "U9") (pin "15") (pinfunction "R232_15") (pintype "passive+no_connect"))
    )
    (net (code "68") (name "unconnected-(U9-RI#-Pad11)") (class "Default")
      (node (ref "U9") (pin "11") (pinfunction "RI#_11") (pintype "passive+no_connect"))
    )
    (net (code "69") (name "unconnected-(U9-RTS#-Pad14)") (class "Default")
      (node (ref "U9") (pin "14") (pinfunction "RTS#_14") (pintype "passive+no_connect"))
    )
    (net (code "70") (name "unconnected-(U10-(ADC2{slash}PCINT10)_PC2-Pad25)") (class "Default")
      (node (ref "U10") (pin "25") (pinfunction "(ADC2/PCINT10)_PC2_25") (pintype "passive+no_connect"))
    )
    (net (code "71") (name "unconnected-(U10-(ADC3{slash}PCINT11)_PC3-Pad27)") (class "Default")
      (node (ref "U10") (pin "27") (pinfunction "(ADC3/PCINT11)_PC3_27") (pintype "passive+no_connect"))
    )
    (net (code "72") (name "~{RESET}") (class "Default")
      (node (ref "BT3") (pin "2") (pinfunction "2_2") (pintype "passive"))
      (node (ref "C33") (pin "2") (pinfunction "2_2") (pintype "passive"))
      (node (ref "JP8") (pin "3") (pinfunction "3_3") (pintype "passive"))
      (node (ref "R20") (pin "1") (pinfunction "1_1") (pintype "passive"))
      (node (ref "U10") (pin "29") (pinfunction "PC6_(~{RESET})_29") (pintype "passive"))
    )
  )
)
